# ArduinoShieldMotor5A.net
KiCad netlist of a schematic drawn in EAGLE
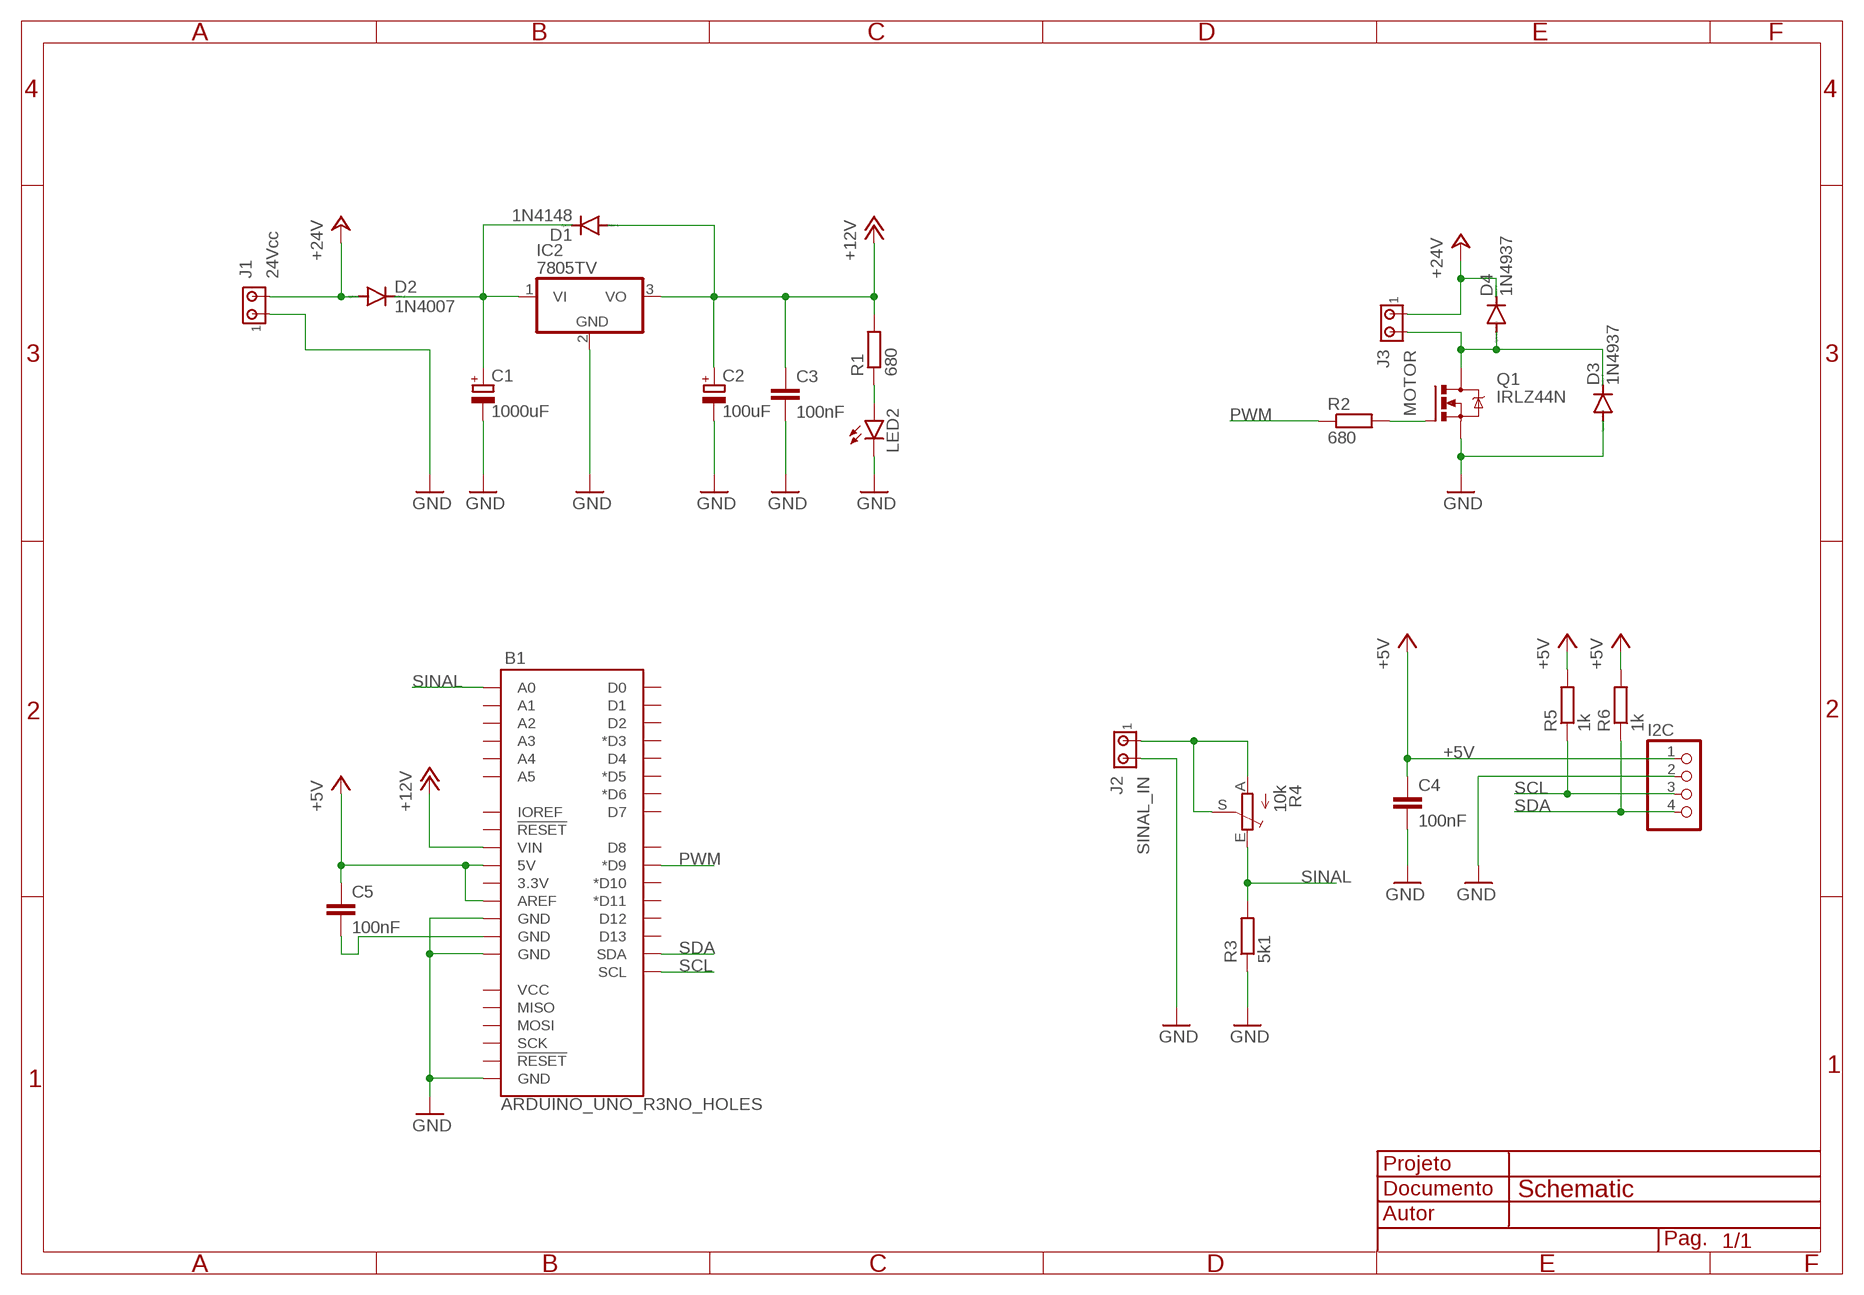
[diagram p0: schematic, sheet 1]

(export (version "E")
  (design (tool "Eeschema 10.0.6"))
  (components
    (comp (ref "B1")
      (value "ARDUINO_UNO_R3NO_HOLES")
      (footprint "eagle-import:ARDUINO_R3_NO_HOLES")
      (libsource (lib "eagle-import") (part "ARDUINO_UNO_R3NO_HOLES"))
    )
    (comp (ref "C1")
      (value "1000uF")
      (footprint "eagle-import:E5-13")
      (libsource (lib "eagle-import") (part "CPOL-EUE5-13"))
    )
    (comp (ref "C2")
      (value "100uF")
      (footprint "eagle-import:E2,5-5")
      (libsource (lib "eagle-import") (part "CPOL-EUE2.5-5"))
    )
    (comp (ref "C3")
      (value "100nF")
      (footprint "eagle-import:C025-025X050")
      (libsource (lib "eagle-import") (part "C-EU025-025X050"))
    )
    (comp (ref "C4")
      (value "100nF")
      (footprint "eagle-import:C025-025X050")
      (libsource (lib "eagle-import") (part "C-EU025-025X050"))
    )
    (comp (ref "C5")
      (value "100nF")
      (footprint "eagle-import:C025-025X050")
      (libsource (lib "eagle-import") (part "C-EU025-025X050"))
    )
    (comp (ref "D1")
      (value "1N4148")
      (footprint "eagle-import:DO35-10")
      (libsource (lib "eagle-import") (part "1N4148DO35-10"))
    )
    (comp (ref "D2")
      (value "1N4007")
      (footprint "eagle-import:DO41-10")
      (libsource (lib "eagle-import") (part "1N4004"))
    )
    (comp (ref "D3")
      (value "1N4937")
      (footprint "eagle-import:DO41-10")
      (libsource (lib "eagle-import") (part "1N4004"))
    )
    (comp (ref "D4")
      (value "1N4937")
      (footprint "eagle-import:DO41-10")
      (libsource (lib "eagle-import") (part "1N4004"))
    )
    (comp (ref "I2C")
      (value "PINHD-1X4")
      (footprint "eagle-import:1X04")
      (libsource (lib "eagle-import") (part "PINHD-1X4"))
    )
    (comp (ref "IC2")
      (value "7805TV")
      (footprint "eagle-import:TO220V")
      (libsource (lib "eagle-import") (part "78TV05"))
    )
    (comp (ref "J1")
      (value "24Vcc")
      (footprint "eagle-import:1X2MTA")
      (libsource (lib "eagle-import") (part "MTA02-156"))
    )
    (comp (ref "J2")
      (value "SINAL_IN")
      (footprint "eagle-import:1X2MTA")
      (libsource (lib "eagle-import") (part "MTA02-156"))
    )
    (comp (ref "J3")
      (value "MOTOR")
      (footprint "eagle-import:1X2MTA")
      (libsource (lib "eagle-import") (part "MTA02-156"))
    )
    (comp (ref "LED2")
      (value "LED3MM")
      (footprint "eagle-import:LED3MM")
      (libsource (lib "eagle-import") (part "LED3MM"))
    )
    (comp (ref "Q1")
      (value "IRLZ44N")
      (footprint "eagle-import:TO220BV")
      (libsource (lib "eagle-import") (part "IRF540"))
    )
    (comp (ref "R1")
      (value "680")
      (footprint "eagle-import:0207_10")
      (libsource (lib "eagle-import") (part "R-EU_0207/10"))
    )
    (comp (ref "R2")
      (value "680")
      (footprint "eagle-import:0207_10")
      (libsource (lib "eagle-import") (part "R-EU_0207/10"))
    )
    (comp (ref "R3")
      (value "5k1")
      (footprint "eagle-import:0207_10")
      (libsource (lib "eagle-import") (part "R-EU_0207/10"))
    )
    (comp (ref "R4")
      (value "10k")
      (footprint "eagle-import:B64Y")
      (libsource (lib "eagle-import") (part "TRIM_EU-B64Y"))
    )
    (comp (ref "R5")
      (value "1k")
      (footprint "eagle-import:0207_10")
      (libsource (lib "eagle-import") (part "R-EU_0207/10"))
    )
    (comp (ref "R6")
      (value "1k")
      (footprint "eagle-import:0207_10")
      (libsource (lib "eagle-import") (part "R-EU_0207/10"))
    )
  )
  (nets
    (net (code "1") (name "+5V") (class "Default")
      (node (ref "B1") (pin "5V") (pinfunction "5V_5V") (pintype "bidirectional"))
      (node (ref "B1") (pin "AREF") (pinfunction "AREF_AREF") (pintype "bidirectional"))
      (node (ref "C4") (pin "1") (pinfunction "1_1") (pintype "passive"))
      (node (ref "C5") (pin "1") (pinfunction "1_1") (pintype "passive"))
      (node (ref "I2C") (pin "1") (pinfunction "1_1") (pintype "passive"))
      (node (ref "R5") (pin "2") (pinfunction "2_2") (pintype "passive"))
      (node (ref "R6") (pin "2") (pinfunction "2_2") (pintype "passive"))
    )
    (net (code "2") (name "+12V") (class "Default")
      (node (ref "B1") (pin "VIN") (pinfunction "VIN_VIN") (pintype "bidirectional"))
      (node (ref "C2") (pin "+") (pinfunction "+_+") (pintype "passive"))
      (node (ref "C3") (pin "1") (pinfunction "1_1") (pintype "passive"))
      (node (ref "D1") (pin "A") (pinfunction "A_A") (pintype "passive"))
      (node (ref "IC2") (pin "3") (pinfunction "VO_3") (pintype "passive"))
      (node (ref "R1") (pin "2") (pinfunction "2_2") (pintype "passive"))
    )
    (net (code "3") (name "+24V") (class "Default")
      (node (ref "D2") (pin "A") (pinfunction "A_A") (pintype "passive"))
      (node (ref "D4") (pin "C") (pinfunction "C_C") (pintype "passive"))
      (node (ref "J1") (pin "2") (pinfunction "2_2") (pintype "passive"))
      (node (ref "J3") (pin "1") (pinfunction "1_1") (pintype "passive"))
    )
    (net (code "4") (name "/PWM") (class "Default")
      (node (ref "B1") (pin "D9") (pinfunction "*D9_D9") (pintype "bidirectional"))
      (node (ref "R2") (pin "1") (pinfunction "1_1") (pintype "passive"))
    )
    (net (code "5") (name "/SCL") (class "Default")
      (node (ref "B1") (pin "SCL") (pinfunction "SCL_SCL") (pintype "bidirectional"))
      (node (ref "I2C") (pin "3") (pinfunction "3_3") (pintype "passive"))
      (node (ref "R5") (pin "1") (pinfunction "1_1") (pintype "passive"))
    )
    (net (code "6") (name "/SDA") (class "Default")
      (node (ref "B1") (pin "SDA") (pinfunction "SDA_SDA") (pintype "bidirectional"))
      (node (ref "I2C") (pin "4") (pinfunction "4_4") (pintype "passive"))
      (node (ref "R6") (pin "1") (pinfunction "1_1") (pintype "passive"))
    )
    (net (code "7") (name "/SINAL") (class "Default")
      (node (ref "B1") (pin "A0") (pinfunction "A0_A0") (pintype "bidirectional"))
      (node (ref "R3") (pin "2") (pinfunction "2_2") (pintype "passive"))
      (node (ref "R4") (pin "E") (pinfunction "E_E") (pintype "passive"))
    )
    (net (code "8") (name "GND") (class "Default")
      (node (ref "B1") (pin "GND@1") (pinfunction "GND_GND@1") (pintype "bidirectional"))
      (node (ref "B1") (pin "GND@2") (pinfunction "GND_GND@2") (pintype "bidirectional"))
      (node (ref "B1") (pin "GND@4") (pinfunction "GND_GND@4") (pintype "bidirectional"))
      (node (ref "C1") (pin "-") (pinfunction "-_-") (pintype "passive"))
      (node (ref "C2") (pin "-") (pinfunction "-_-") (pintype "passive"))
      (node (ref "C3") (pin "2") (pinfunction "2_2") (pintype "passive"))
      (node (ref "C4") (pin "2") (pinfunction "2_2") (pintype "passive"))
      (node (ref "D3") (pin "A") (pinfunction "A_A") (pintype "passive"))
      (node (ref "I2C") (pin "2") (pinfunction "2_2") (pintype "passive"))
      (node (ref "IC2") (pin "2") (pinfunction "GND_2") (pintype "passive"))
      (node (ref "J1") (pin "1") (pinfunction "1_1") (pintype "passive"))
      (node (ref "J2") (pin "2") (pinfunction "2_2") (pintype "passive"))
      (node (ref "LED2") (pin "K") (pinfunction "C_K") (pintype "passive"))
      (node (ref "Q1") (pin "S") (pinfunction "S_S") (pintype "passive"))
      (node (ref "R3") (pin "1") (pinfunction "1_1") (pintype "passive"))
    )
    (net (code "9") (name "Net-(B1-GND-PadGND@3)") (class "Default")
      (node (ref "B1") (pin "GND@3") (pinfunction "GND_GND@3") (pintype "bidirectional"))
      (node (ref "C5") (pin "2") (pinfunction "2_2") (pintype "passive"))
    )
    (net (code "10") (name "Net-(D3-PadC)") (class "Default")
      (node (ref "D3") (pin "C") (pinfunction "C_C") (pintype "passive"))
      (node (ref "D4") (pin "A") (pinfunction "A_A") (pintype "passive"))
      (node (ref "J3") (pin "2") (pinfunction "2_2") (pintype "passive"))
      (node (ref "Q1") (pin "D") (pinfunction "D_D") (pintype "passive"))
    )
    (net (code "11") (name "Net-(IC2-VI)") (class "Default")
      (node (ref "C1") (pin "+") (pinfunction "+_+") (pintype "passive"))
      (node (ref "D1") (pin "C") (pinfunction "C_C") (pintype "passive"))
      (node (ref "D2") (pin "C") (pinfunction "C_C") (pintype "passive"))
      (node (ref "IC2") (pin "1") (pinfunction "VI_1") (pintype "input"))
    )
    (net (code "12") (name "Net-(J2-Pad1)") (class "Default")
      (node (ref "J2") (pin "1") (pinfunction "1_1") (pintype "passive"))
      (node (ref "R4") (pin "A") (pinfunction "A_A") (pintype "passive"))
      (node (ref "R4") (pin "S") (pinfunction "S_S") (pintype "passive"))
    )
    (net (code "13") (name "Net-(LED2-PadA)") (class "Default")
      (node (ref "LED2") (pin "A") (pinfunction "A_A") (pintype "passive"))
      (node (ref "R1") (pin "1") (pinfunction "1_1") (pintype "passive"))
    )
    (net (code "14") (name "Net-(Q1-PadG)") (class "Default")
      (node (ref "Q1") (pin "G") (pinfunction "G_G") (pintype "passive"))
      (node (ref "R2") (pin "2") (pinfunction "2_2") (pintype "passive"))
    )
    (net (code "15") (name "unconnected-(B1-*D3-PadD3)") (class "Default")
      (node (ref "B1") (pin "D3") (pinfunction "*D3_D3") (pintype "bidirectional"))
    )
    (net (code "16") (name "unconnected-(B1-*D5-PadD5)") (class "Default")
      (node (ref "B1") (pin "D5") (pinfunction "*D5_D5") (pintype "bidirectional"))
    )
    (net (code "17") (name "unconnected-(B1-*D6-PadD6)") (class "Default")
      (node (ref "B1") (pin "D6") (pinfunction "*D6_D6") (pintype "bidirectional"))
    )
    (net (code "18") (name "unconnected-(B1-*D10-PadD10)") (class "Default")
      (node (ref "B1") (pin "D10") (pinfunction "*D10_D10") (pintype "bidirectional"))
    )
    (net (code "19") (name "unconnected-(B1-*D11-PadD11)") (class "Default")
      (node (ref "B1") (pin "D11") (pinfunction "*D11_D11") (pintype "bidirectional"))
    )
    (net (code "20") (name "unconnected-(B1-Pad3.3V)") (class "Default")
      (node (ref "B1") (pin "3.3V") (pinfunction "3.3V_3.3V") (pintype "bidirectional"))
    )
    (net (code "21") (name "unconnected-(B1-PadA1)") (class "Default")
      (node (ref "B1") (pin "A1") (pinfunction "A1_A1") (pintype "bidirectional"))
    )
    (net (code "22") (name "unconnected-(B1-PadA2)") (class "Default")
      (node (ref "B1") (pin "A2") (pinfunction "A2_A2") (pintype "bidirectional"))
    )
    (net (code "23") (name "unconnected-(B1-PadA3)") (class "Default")
      (node (ref "B1") (pin "A3") (pinfunction "A3_A3") (pintype "bidirectional"))
    )
    (net (code "24") (name "unconnected-(B1-PadA4)") (class "Default")
      (node (ref "B1") (pin "A4") (pinfunction "A4_A4") (pintype "bidirectional"))
    )
    (net (code "25") (name "unconnected-(B1-PadA5)") (class "Default")
      (node (ref "B1") (pin "A5") (pinfunction "A5_A5") (pintype "bidirectional"))
    )
    (net (code "26") (name "unconnected-(B1-PadD0)") (class "Default")
      (node (ref "B1") (pin "D0") (pinfunction "D0_D0") (pintype "bidirectional"))
    )
    (net (code "27") (name "unconnected-(B1-PadD1)") (class "Default")
      (node (ref "B1") (pin "D1") (pinfunction "D1_D1") (pintype "bidirectional"))
    )
    (net (code "28") (name "unconnected-(B1-PadD2)") (class "Default")
      (node (ref "B1") (pin "D2") (pinfunction "D2_D2") (pintype "bidirectional"))
    )
    (net (code "29") (name "unconnected-(B1-PadD4)") (class "Default")
      (node (ref "B1") (pin "D4") (pinfunction "D4_D4") (pintype "bidirectional"))
    )
    (net (code "30") (name "unconnected-(B1-PadD7)") (class "Default")
      (node (ref "B1") (pin "D7") (pinfunction "D7_D7") (pintype "bidirectional"))
    )
    (net (code "31") (name "unconnected-(B1-PadD8)") (class "Default")
      (node (ref "B1") (pin "D8") (pinfunction "D8_D8") (pintype "bidirectional"))
    )
    (net (code "32") (name "unconnected-(B1-PadD12)") (class "Default")
      (node (ref "B1") (pin "D12") (pinfunction "D12_D12") (pintype "bidirectional"))
    )
    (net (code "33") (name "unconnected-(B1-PadD13)") (class "Default")
      (node (ref "B1") (pin "D13") (pinfunction "D13_D13") (pintype "bidirectional"))
    )
    (net (code "34") (name "unconnected-(B1-PadIOREF)") (class "Default")
      (node (ref "B1") (pin "IOREF") (pinfunction "IOREF_IOREF") (pintype "bidirectional"))
    )
    (net (code "35") (name "unconnected-(B1-PadMISO)") (class "Default")
      (node (ref "B1") (pin "MISO") (pinfunction "MISO_MISO") (pintype "bidirectional"))
    )
    (net (code "36") (name "unconnected-(B1-PadMOSI)") (class "Default")
      (node (ref "B1") (pin "MOSI") (pinfunction "MOSI_MOSI") (pintype "bidirectional"))
    )
    (net (code "37") (name "unconnected-(B1-PadSCK)") (class "Default")
      (node (ref "B1") (pin "SCK") (pinfunction "SCK_SCK") (pintype "bidirectional"))
    )
    (net (code "38") (name "unconnected-(B1-PadVCC)") (class "Default")
      (node (ref "B1") (pin "VCC") (pinfunction "VCC_VCC") (pintype "bidirectional"))
    )
    (net (code "39") (name "unconnected-(B1-~{RESET}-PadRESET@1)") (class "Default")
      (node (ref "B1") (pin "RESET@1") (pinfunction "~{RESET}_RESET@1") (pintype "bidirectional"))
    )
    (net (code "40") (name "unconnected-(B1-~{RESET}-PadRESET@2)") (class "Default")
      (node (ref "B1") (pin "RESET@2") (pinfunction "~{RESET}_RESET@2") (pintype "bidirectional"))
    )
  )
)
